# Led.net
KiCad netlist of a schematic drawn in Altium Designer
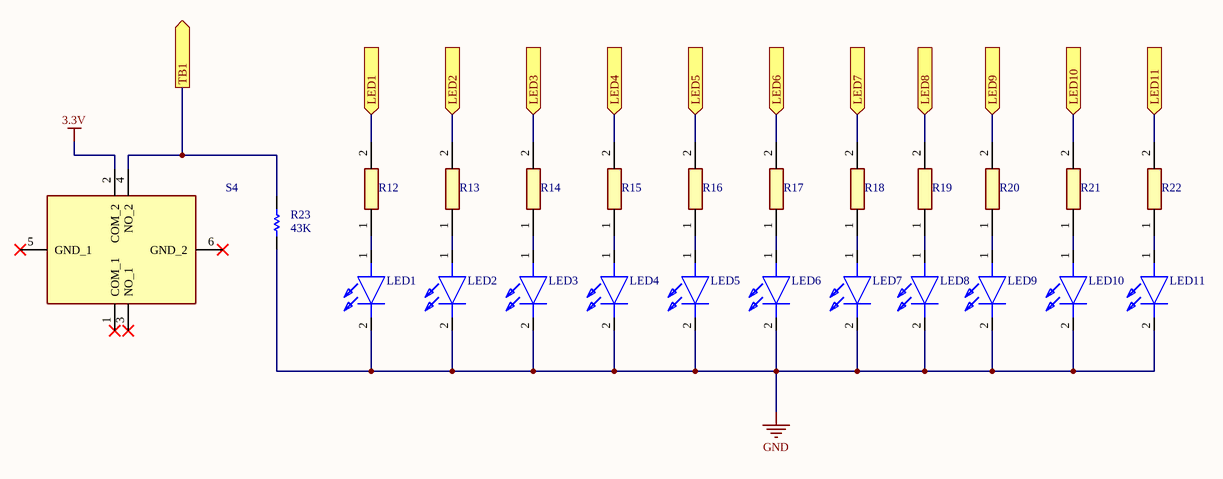
[diagram p0: Led.SchDoc]

(export (version "E")
  (design (tool "Eeschema 10.0.6"))
  (components
    (comp (ref "LED1")
      (value "598-2105-107F")
      (footprint "SamacSys:5982105107F")
      (description "LED")
      (fields (field (name "MOUSER PART NUMBER") "645-598-2105-107F"))
      (libsource (lib "*") (part "598-2105-107F"))
    )
    (comp (ref "LED2")
      (value "598-2105-107F")
      (footprint "SamacSys:5982105107F")
      (description "LED")
      (fields (field (name "MOUSER PART NUMBER") "645-598-2105-107F"))
      (libsource (lib "*") (part "598-2105-107F"))
    )
    (comp (ref "LED3")
      (value "598-2105-107F")
      (footprint "SamacSys:5982105107F")
      (description "LED")
      (fields (field (name "MOUSER PART NUMBER") "645-598-2105-107F"))
      (libsource (lib "*") (part "598-2105-107F"))
    )
    (comp (ref "LED4")
      (value "598-2105-107F")
      (footprint "SamacSys:5982105107F")
      (description "LED")
      (fields (field (name "MOUSER PART NUMBER") "645-598-2105-107F"))
      (libsource (lib "*") (part "598-2105-107F"))
    )
    (comp (ref "LED5")
      (value "598-2105-107F")
      (footprint "SamacSys:5982105107F")
      (description "LED")
      (fields (field (name "MOUSER PART NUMBER") "645-598-2105-107F"))
      (libsource (lib "*") (part "598-2105-107F"))
    )
    (comp (ref "LED6")
      (value "598-2105-107F")
      (footprint "SamacSys:5982105107F")
      (description "LED")
      (fields (field (name "MOUSER PART NUMBER") "645-598-2105-107F"))
      (libsource (lib "*") (part "598-2105-107F"))
    )
    (comp (ref "LED7")
      (value "598-2105-107F")
      (footprint "SamacSys:5982105107F")
      (description "LED")
      (fields (field (name "MOUSER PART NUMBER") "645-598-2105-107F"))
      (libsource (lib "*") (part "598-2105-107F"))
    )
    (comp (ref "LED8")
      (value "598-2105-107F")
      (footprint "SamacSys:5982105107F")
      (description "LED")
      (fields (field (name "MOUSER PART NUMBER") "645-598-2105-107F"))
      (libsource (lib "*") (part "598-2105-107F"))
    )
    (comp (ref "LED9")
      (value "598-2105-107F")
      (footprint "SamacSys:5982105107F")
      (description "LED")
      (fields (field (name "MOUSER PART NUMBER") "645-598-2105-107F"))
      (libsource (lib "*") (part "598-2105-107F"))
    )
    (comp (ref "LED10")
      (value "598-2105-107F")
      (footprint "SamacSys:5982105107F")
      (description "LED")
      (fields (field (name "MOUSER PART NUMBER") "645-598-2105-107F"))
      (libsource (lib "*") (part "598-2105-107F"))
    )
    (comp (ref "LED11")
      (value "598-2105-107F")
      (footprint "SamacSys:5982105107F")
      (description "LED")
      (fields (field (name "MOUSER PART NUMBER") "645-598-2105-107F"))
      (libsource (lib "*") (part "598-2105-107F"))
    )
    (comp (ref "R12")
      (value "ERJ-U06J102V")
      (footprint "SamacSys:ERJS06_U06_(0805)")
      (description "Resistor")
      (fields (field (name "MOUSER PART NUMBER") "667-ERJ-U06J102V"))
      (libsource (lib "*") (part "ERJ-U06J102V"))
    )
    (comp (ref "R13")
      (value "ERJ-U06J102V")
      (footprint "SamacSys:ERJS06_U06_(0805)")
      (description "Resistor")
      (fields (field (name "MOUSER PART NUMBER") "667-ERJ-U06J102V"))
      (libsource (lib "*") (part "ERJ-U06J102V"))
    )
    (comp (ref "R14")
      (value "ERJ-U06J102V")
      (footprint "SamacSys:ERJS06_U06_(0805)")
      (description "Resistor")
      (fields (field (name "MOUSER PART NUMBER") "667-ERJ-U06J102V"))
      (libsource (lib "*") (part "ERJ-U06J102V"))
    )
    (comp (ref "R15")
      (value "ERJ-U06J102V")
      (footprint "SamacSys:ERJS06_U06_(0805)")
      (description "Resistor")
      (fields (field (name "MOUSER PART NUMBER") "667-ERJ-U06J102V"))
      (libsource (lib "*") (part "ERJ-U06J102V"))
    )
    (comp (ref "R16")
      (value "ERJ-U06J102V")
      (footprint "SamacSys:ERJS06_U06_(0805)")
      (description "Resistor")
      (fields (field (name "MOUSER PART NUMBER") "667-ERJ-U06J102V"))
      (libsource (lib "*") (part "ERJ-U06J102V"))
    )
    (comp (ref "R17")
      (value "ERJ-U06J102V")
      (footprint "SamacSys:ERJS06_U06_(0805)")
      (description "Resistor")
      (fields (field (name "MOUSER PART NUMBER") "667-ERJ-U06J102V"))
      (libsource (lib "*") (part "ERJ-U06J102V"))
    )
    (comp (ref "R18")
      (value "ERJ-U06J102V")
      (footprint "SamacSys:ERJS06_U06_(0805)")
      (description "Resistor")
      (fields (field (name "MOUSER PART NUMBER") "667-ERJ-U06J102V"))
      (libsource (lib "*") (part "ERJ-U06J102V"))
    )
    (comp (ref "R19")
      (value "ERJ-U06J102V")
      (footprint "SamacSys:ERJS06_U06_(0805)")
      (description "Resistor")
      (fields (field (name "MOUSER PART NUMBER") "667-ERJ-U06J102V"))
      (libsource (lib "*") (part "ERJ-U06J102V"))
    )
    (comp (ref "R20")
      (value "ERJ-U06J102V")
      (footprint "SamacSys:ERJS06_U06_(0805)")
      (description "Resistor")
      (fields (field (name "MOUSER PART NUMBER") "667-ERJ-U06J102V"))
      (libsource (lib "*") (part "ERJ-U06J102V"))
    )
    (comp (ref "R21")
      (value "ERJ-U06J102V")
      (footprint "SamacSys:ERJS06_U06_(0805)")
      (description "Resistor")
      (fields (field (name "MOUSER PART NUMBER") "667-ERJ-U06J102V"))
      (libsource (lib "*") (part "ERJ-U06J102V"))
    )
    (comp (ref "R22")
      (value "ERJ-U06J102V")
      (footprint "SamacSys:ERJS06_U06_(0805)")
      (description "Resistor")
      (fields (field (name "MOUSER PART NUMBER") "667-ERJ-U06J102V"))
      (libsource (lib "*") (part "ERJ-U06J102V"))
    )
    (comp (ref "R23")
      (value "43K")
      (footprint "RESC1608X55X30ML20T20")
      (fields (field (name "PART NUMBER") "ERA3AEB433V") (field (name "MANUFACTURER") "Panasonic"))
      (libsource (lib "Altium Content Vault") (part "RES"))
    )
    (comp (ref "S4")
      (value "PTS526SMG20SMTR21_LFS")
      (footprint "SamacSys:PTS526SMG20SMTR21LFS")
      (description "Switch")
      (fields
        (field (name "MANUFACTURER_PART_NUMBER") "PTS526SMG20SMTR21 LFS")
        (field (name "MOUSER PART NUMBER") "611-PTS526SMG20S21LF")
      )
      (libsource (lib "SamacSys") (part "PTS526SMG20SMTR21_LFS"))
    )
  )
  (nets
    (net (code "1") (name "/LED1") (class "Default")
      (node (ref "R12") (pin "2") (pinfunction "2_2") (pintype "passive"))
    )
    (net (code "2") (name "/LED2") (class "Default")
      (node (ref "R13") (pin "2") (pinfunction "2_2") (pintype "passive"))
    )
    (net (code "3") (name "/LED3") (class "Default")
      (node (ref "R14") (pin "2") (pinfunction "2_2") (pintype "passive"))
    )
    (net (code "4") (name "/LED4") (class "Default")
      (node (ref "R15") (pin "2") (pinfunction "2_2") (pintype "passive"))
    )
    (net (code "5") (name "/LED5") (class "Default")
      (node (ref "R16") (pin "2") (pinfunction "2_2") (pintype "passive"))
    )
    (net (code "6") (name "/LED6") (class "Default")
      (node (ref "R17") (pin "2") (pinfunction "2_2") (pintype "passive"))
    )
    (net (code "7") (name "/LED7") (class "Default")
      (node (ref "R18") (pin "2") (pinfunction "2_2") (pintype "passive"))
    )
    (net (code "8") (name "/LED8") (class "Default")
      (node (ref "R19") (pin "2") (pinfunction "2_2") (pintype "passive"))
    )
    (net (code "9") (name "/LED9") (class "Default")
      (node (ref "R20") (pin "2") (pinfunction "2_2") (pintype "passive"))
    )
    (net (code "10") (name "/LED10") (class "Default")
      (node (ref "R21") (pin "2") (pinfunction "2_2") (pintype "passive"))
    )
    (net (code "11") (name "/LED11") (class "Default")
      (node (ref "R22") (pin "2") (pinfunction "2_2") (pintype "passive"))
    )
    (net (code "12") (name "/TB1") (class "Default")
      (node (ref "R23") (pin "2") (pinfunction "2_2") (pintype "passive"))
      (node (ref "S4") (pin "4") (pinfunction "NO_2_4") (pintype "passive"))
    )
    (net (code "13") (name "3.3V") (class "Default")
      (node (ref "S4") (pin "2") (pinfunction "COM_2_2") (pintype "passive"))
    )
    (net (code "14") (name "GND") (class "Default")
      (node (ref "LED1") (pin "2") (pinfunction "K_2") (pintype "passive"))
      (node (ref "LED10") (pin "2") (pinfunction "K_2") (pintype "passive"))
      (node (ref "LED11") (pin "2") (pinfunction "K_2") (pintype "passive"))
      (node (ref "LED2") (pin "2") (pinfunction "K_2") (pintype "passive"))
      (node (ref "LED3") (pin "2") (pinfunction "K_2") (pintype "passive"))
      (node (ref "LED4") (pin "2") (pinfunction "K_2") (pintype "passive"))
      (node (ref "LED5") (pin "2") (pinfunction "K_2") (pintype "passive"))
      (node (ref "LED6") (pin "2") (pinfunction "K_2") (pintype "passive"))
      (node (ref "LED7") (pin "2") (pinfunction "K_2") (pintype "passive"))
      (node (ref "LED8") (pin "2") (pinfunction "K_2") (pintype "passive"))
      (node (ref "LED9") (pin "2") (pinfunction "K_2") (pintype "passive"))
      (node (ref "R23") (pin "1") (pinfunction "1_1") (pintype "passive"))
    )
    (net (code "15") (name "Net-(LED1-A)") (class "Default")
      (node (ref "LED1") (pin "1") (pinfunction "A_1") (pintype "passive"))
      (node (ref "R12") (pin "1") (pinfunction "1_1") (pintype "passive"))
    )
    (net (code "16") (name "Net-(LED2-A)") (class "Default")
      (node (ref "LED2") (pin "1") (pinfunction "A_1") (pintype "passive"))
      (node (ref "R13") (pin "1") (pinfunction "1_1") (pintype "passive"))
    )
    (net (code "17") (name "Net-(LED3-A)") (class "Default")
      (node (ref "LED3") (pin "1") (pinfunction "A_1") (pintype "passive"))
      (node (ref "R14") (pin "1") (pinfunction "1_1") (pintype "passive"))
    )
    (net (code "18") (name "Net-(LED4-A)") (class "Default")
      (node (ref "LED4") (pin "1") (pinfunction "A_1") (pintype "passive"))
      (node (ref "R15") (pin "1") (pinfunction "1_1") (pintype "passive"))
    )
    (net (code "19") (name "Net-(LED5-A)") (class "Default")
      (node (ref "LED5") (pin "1") (pinfunction "A_1") (pintype "passive"))
      (node (ref "R16") (pin "1") (pinfunction "1_1") (pintype "passive"))
    )
    (net (code "20") (name "Net-(LED6-A)") (class "Default")
      (node (ref "LED6") (pin "1") (pinfunction "A_1") (pintype "passive"))
      (node (ref "R17") (pin "1") (pinfunction "1_1") (pintype "passive"))
    )
    (net (code "21") (name "Net-(LED7-A)") (class "Default")
      (node (ref "LED7") (pin "1") (pinfunction "A_1") (pintype "passive"))
      (node (ref "R18") (pin "1") (pinfunction "1_1") (pintype "passive"))
    )
    (net (code "22") (name "Net-(LED8-A)") (class "Default")
      (node (ref "LED8") (pin "1") (pinfunction "A_1") (pintype "passive"))
      (node (ref "R19") (pin "1") (pinfunction "1_1") (pintype "passive"))
    )
    (net (code "23") (name "Net-(LED9-A)") (class "Default")
      (node (ref "LED9") (pin "1") (pinfunction "A_1") (pintype "passive"))
      (node (ref "R20") (pin "1") (pinfunction "1_1") (pintype "passive"))
    )
    (net (code "24") (name "Net-(LED10-A)") (class "Default")
      (node (ref "LED10") (pin "1") (pinfunction "A_1") (pintype "passive"))
      (node (ref "R21") (pin "1") (pinfunction "1_1") (pintype "passive"))
    )
    (net (code "25") (name "Net-(LED11-A)") (class "Default")
      (node (ref "LED11") (pin "1") (pinfunction "A_1") (pintype "passive"))
      (node (ref "R22") (pin "1") (pinfunction "1_1") (pintype "passive"))
    )
    (net (code "26") (name "unconnected-(S4-COM_1-Pad1)") (class "Default")
      (node (ref "S4") (pin "1") (pinfunction "COM_1_1") (pintype "passive+no_connect"))
    )
    (net (code "27") (name "unconnected-(S4-GND_1-Pad5)") (class "Default")
      (node (ref "S4") (pin "5") (pinfunction "GND_1_5") (pintype "passive+no_connect"))
    )
    (net (code "28") (name "unconnected-(S4-GND_2-Pad6)") (class "Default")
      (node (ref "S4") (pin "6") (pinfunction "GND_2_6") (pintype "passive+no_connect"))
    )
    (net (code "29") (name "unconnected-(S4-NO_1-Pad3)") (class "Default")
      (node (ref "S4") (pin "3") (pinfunction "NO_1_3") (pintype "passive+no_connect"))
    )
  )
)
